# BadAssbasSSynth.net
KiCad netlist of a schematic drawn in EAGLE
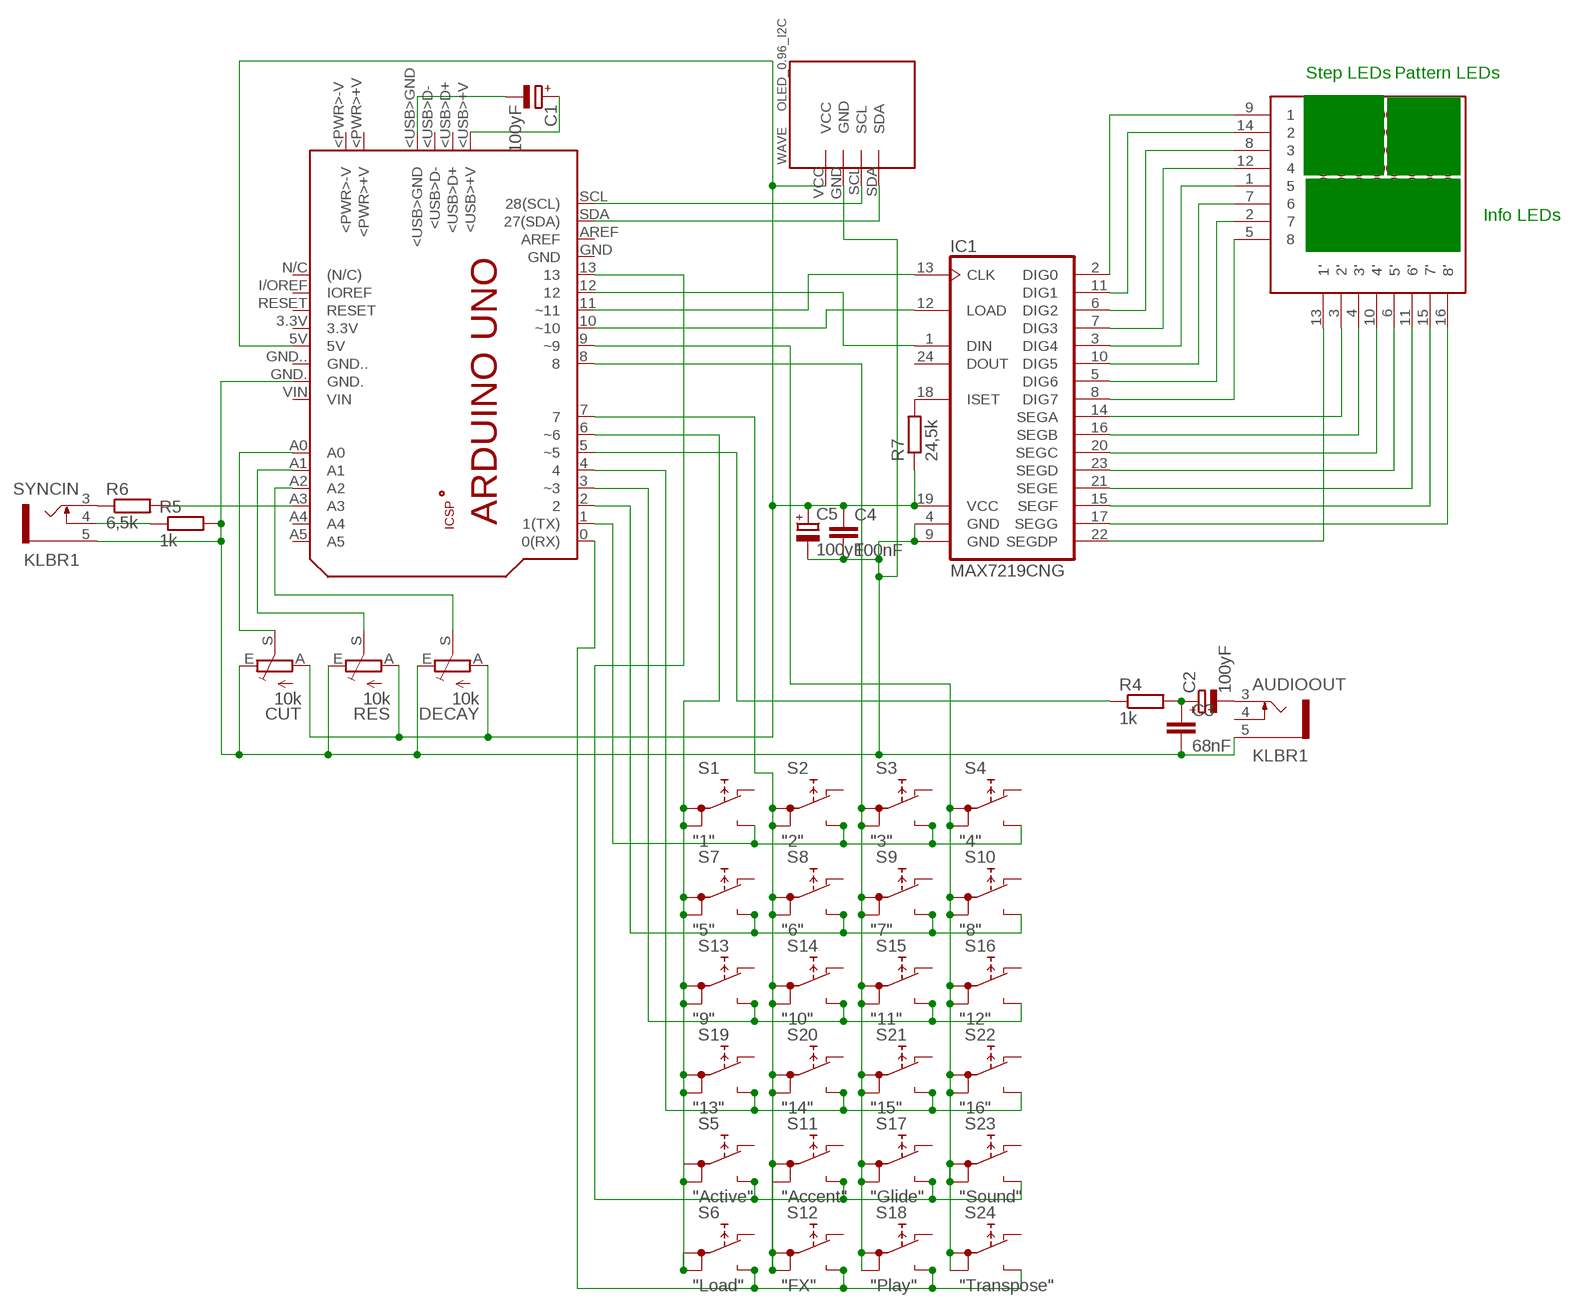
[diagram p0: schematic, sheet 1]

(export (version "E")
  (design (tool "Eeschema 10.0.6"))
  (components
    (comp (ref "AUDIOOUT")
      (value "KLBR1")
      (footprint "eagle-import:KLBR1")
      (fields (field (name "MPN") "KLBR 1"))
      (libsource (lib "eagle-import") (part "KLBR?1"))
    )
    (comp (ref "C1")
      (value "100yF")
      (footprint "eagle-import:E2,5-6E")
      (libsource (lib "eagle-import") (part "CPOL-EUE2,5-6E"))
    )
    (comp (ref "C2")
      (value "100yF")
      (footprint "eagle-import:E2,5-6E")
      (libsource (lib "eagle-import") (part "CPOL-EUE2,5-6E"))
    )
    (comp (ref "C3")
      (value "68nF")
      (footprint "eagle-import:C025-025X050")
      (libsource (lib "eagle-import") (part "C-EU025-025X050"))
    )
    (comp (ref "C4")
      (value "100nF")
      (footprint "eagle-import:C025-025X050")
      (libsource (lib "eagle-import") (part "C-EU025-025X050"))
    )
    (comp (ref "C5")
      (value "100yF")
      (footprint "eagle-import:E2,5-6E")
      (libsource (lib "eagle-import") (part "CPOL-EUE2,5-6E"))
    )
    (comp (ref "CUT")
      (value "10k")
      (footprint "eagle-import:CIP20C-6MM")
      (libsource (lib "eagle-import") (part "TRIM_EU-CIP20C-6MM"))
    )
    (comp (ref "DECAY")
      (value "10k")
      (footprint "eagle-import:CIP20C-6MM")
      (libsource (lib "eagle-import") (part "TRIM_EU-CIP20C-6MM"))
    )
    (comp (ref "IC1")
      (value "MAX7219CNG")
      (footprint "eagle-import:DIL24-3")
      (fields (field (name "MF") "MAXIM"))
      (libsource (lib "eagle-import") (part "MAX7219CNG"))
    )
    (comp (ref "PCB1")
      (value "ARDUINO_UNO")
      (footprint "eagle-import:ARDUINO_UNO")
      (libsource (lib "eagle-import") (part "ARDUINO_UNO"))
    )
    (comp (ref "R4")
      (value "1k")
      (footprint "eagle-import:0204_7")
      (libsource (lib "eagle-import") (part "R-EU_0204/7"))
    )
    (comp (ref "R5")
      (value "1k")
      (footprint "eagle-import:0204_7")
      (libsource (lib "eagle-import") (part "R-EU_0204/7"))
    )
    (comp (ref "R6")
      (value "6,5k")
      (footprint "eagle-import:0204_7")
      (libsource (lib "eagle-import") (part "R-EU_0204/7"))
    )
    (comp (ref "R7")
      (value "24,5k")
      (footprint "eagle-import:0204_7")
      (libsource (lib "eagle-import") (part "R-EU_0204/7"))
    )
    (comp (ref "RES")
      (value "10k")
      (footprint "eagle-import:CIP20C-6MM")
      (libsource (lib "eagle-import") (part "TRIM_EU-CIP20C-6MM"))
    )
    (comp (ref "S1")
      (value "\"1\"")
      (footprint "eagle-import:5501")
      (libsource (lib "eagle-import") (part "55?01"))
    )
    (comp (ref "S2")
      (value "\"2\"")
      (footprint "eagle-import:5501")
      (libsource (lib "eagle-import") (part "55?01"))
    )
    (comp (ref "S3")
      (value "\"3\"")
      (footprint "eagle-import:5501")
      (libsource (lib "eagle-import") (part "55?01"))
    )
    (comp (ref "S4")
      (value "\"4\"")
      (footprint "eagle-import:5501")
      (libsource (lib "eagle-import") (part "55?01"))
    )
    (comp (ref "S5")
      (value "\"Active\"")
      (footprint "eagle-import:5501")
      (libsource (lib "eagle-import") (part "55?01"))
    )
    (comp (ref "S6")
      (value "\"Load\"")
      (footprint "eagle-import:5501")
      (libsource (lib "eagle-import") (part "55?01"))
    )
    (comp (ref "S7")
      (value "\"5\"")
      (footprint "eagle-import:5501")
      (libsource (lib "eagle-import") (part "55?01"))
    )
    (comp (ref "S8")
      (value "\"6\"")
      (footprint "eagle-import:5501")
      (libsource (lib "eagle-import") (part "55?01"))
    )
    (comp (ref "S9")
      (value "\"7\"")
      (footprint "eagle-import:5501")
      (libsource (lib "eagle-import") (part "55?01"))
    )
    (comp (ref "S10")
      (value "\"8\"")
      (footprint "eagle-import:5501")
      (libsource (lib "eagle-import") (part "55?01"))
    )
    (comp (ref "S11")
      (value "\"Accent\"")
      (footprint "eagle-import:5501")
      (libsource (lib "eagle-import") (part "55?01"))
    )
    (comp (ref "S12")
      (value "\"FX\"")
      (footprint "eagle-import:5501")
      (libsource (lib "eagle-import") (part "55?01"))
    )
    (comp (ref "S13")
      (value "\"9\"")
      (footprint "eagle-import:5501")
      (libsource (lib "eagle-import") (part "55?01"))
    )
    (comp (ref "S14")
      (value "\"10\"")
      (footprint "eagle-import:5501")
      (libsource (lib "eagle-import") (part "55?01"))
    )
    (comp (ref "S15")
      (value "\"11\"")
      (footprint "eagle-import:5501")
      (libsource (lib "eagle-import") (part "55?01"))
    )
    (comp (ref "S16")
      (value "\"12\"")
      (footprint "eagle-import:5501")
      (libsource (lib "eagle-import") (part "55?01"))
    )
    (comp (ref "S17")
      (value "\"Glide\"")
      (footprint "eagle-import:5501")
      (libsource (lib "eagle-import") (part "55?01"))
    )
    (comp (ref "S18")
      (value "\"Play\"")
      (footprint "eagle-import:5501")
      (libsource (lib "eagle-import") (part "55?01"))
    )
    (comp (ref "S19")
      (value "\"13\"")
      (footprint "eagle-import:5501")
      (libsource (lib "eagle-import") (part "55?01"))
    )
    (comp (ref "S20")
      (value "\"14\"")
      (footprint "eagle-import:5501")
      (libsource (lib "eagle-import") (part "55?01"))
    )
    (comp (ref "S21")
      (value "\"15\"")
      (footprint "eagle-import:5501")
      (libsource (lib "eagle-import") (part "55?01"))
    )
    (comp (ref "S22")
      (value "\"16\"")
      (footprint "eagle-import:5501")
      (libsource (lib "eagle-import") (part "55?01"))
    )
    (comp (ref "S23")
      (value "\"Sound\"")
      (footprint "eagle-import:5501")
      (libsource (lib "eagle-import") (part "55?01"))
    )
    (comp (ref "S24")
      (value "\"Transpose\"")
      (footprint "eagle-import:5501")
      (libsource (lib "eagle-import") (part "55?01"))
    )
    (comp (ref "SYNCIN")
      (value "KLBR1")
      (footprint "eagle-import:KLBR1")
      (fields (field (name "MPN") "KLBR 1"))
      (libsource (lib "eagle-import") (part "KLBR?1"))
    )
    (comp (ref "U$2")
      (value "NFM-12881BG-11")
      (footprint "eagle-import:NFM-12881BG-11")
      (libsource (lib "eagle-import") (part "NFM-12881BG-11"))
    )
    (comp (ref "WAVE")
      (value "OLED_0.96_I2C")
      (footprint "eagle-import:OLED_0.96_I2C")
      (libsource (lib "eagle-import") (part "OLED_0.96_I2C"))
    )
  )
  (nets
    (net (code "1") (name "Net-(AUDIOOUT-Pad3)") (class "Default")
      (node (ref "AUDIOOUT") (pin "3") (pinfunction "3_3") (pintype "passive"))
      (node (ref "C2") (pin "-") (pinfunction "-_-") (pintype "passive"))
    )
    (net (code "2") (name "Net-(AUDIOOUT-Pad5)") (class "Default")
      (node (ref "AUDIOOUT") (pin "5") (pinfunction "5_5") (pintype "passive"))
      (node (ref "C3") (pin "2") (pinfunction "2_2") (pintype "passive"))
      (node (ref "C4") (pin "2") (pinfunction "2_2") (pintype "passive"))
      (node (ref "C5") (pin "-") (pinfunction "-_-") (pintype "passive"))
      (node (ref "CUT") (pin "E") (pinfunction "E_E") (pintype "passive"))
      (node (ref "DECAY") (pin "E") (pinfunction "E_E") (pintype "passive"))
      (node (ref "IC1") (pin "4") (pinfunction "GND_4") (pintype "power_in"))
      (node (ref "IC1") (pin "9") (pinfunction "GND_9") (pintype "power_in"))
      (node (ref "PCB1") (pin "GND.") (pinfunction "GND._GND.") (pintype "bidirectional"))
      (node (ref "R5") (pin "2") (pinfunction "2_2") (pintype "passive"))
      (node (ref "RES") (pin "E") (pinfunction "E_E") (pintype "passive"))
      (node (ref "SYNCIN") (pin "5") (pinfunction "5_5") (pintype "passive"))
      (node (ref "WAVE") (pin "GND") (pinfunction "GND_GND") (pintype "bidirectional"))
    )
    (net (code "3") (name "Net-(C1-Pad+)") (class "Default")
      (node (ref "C1") (pin "+") (pinfunction "+_+") (pintype "passive"))
      (node (ref "PCB1") (pin "<USB>+V") (pinfunction "<USB>+V_<USB>+V") (pintype "bidirectional"))
    )
    (net (code "4") (name "Net-(C1-Pad-)") (class "Default")
      (node (ref "C1") (pin "-") (pinfunction "-_-") (pintype "passive"))
      (node (ref "PCB1") (pin "<USB>GND") (pinfunction "<USB>GND_<USB>GND") (pintype "bidirectional"))
    )
    (net (code "5") (name "Net-(C2-Pad+)") (class "Default")
      (node (ref "C2") (pin "+") (pinfunction "+_+") (pintype "passive"))
      (node (ref "C3") (pin "1") (pinfunction "1_1") (pintype "passive"))
      (node (ref "R4") (pin "2") (pinfunction "2_2") (pintype "passive"))
    )
    (net (code "6") (name "Net-(CUT-PadS)") (class "Default")
      (node (ref "CUT") (pin "S") (pinfunction "S_S") (pintype "passive"))
      (node (ref "PCB1") (pin "A0") (pinfunction "A0_A0") (pintype "bidirectional"))
    )
    (net (code "7") (name "Net-(DECAY-PadS)") (class "Default")
      (node (ref "DECAY") (pin "S") (pinfunction "S_S") (pintype "passive"))
      (node (ref "PCB1") (pin "A2") (pinfunction "A2_A2") (pintype "bidirectional"))
    )
    (net (code "8") (name "Net-(IC1-CLK)") (class "Default")
      (node (ref "IC1") (pin "13") (pinfunction "CLK_13") (pintype "input"))
      (node (ref "PCB1") (pin "11") (pinfunction "~{11}_11") (pintype "bidirectional"))
    )
    (net (code "9") (name "Net-(IC1-DIG0)") (class "Default")
      (node (ref "IC1") (pin "2") (pinfunction "DIG0_2") (pintype "output"))
      (node (ref "U$2") (pin "9") (pinfunction "1_9") (pintype "input"))
    )
    (net (code "10") (name "Net-(IC1-DIG1)") (class "Default")
      (node (ref "IC1") (pin "11") (pinfunction "DIG1_11") (pintype "output"))
      (node (ref "U$2") (pin "14") (pinfunction "2_14") (pintype "input"))
    )
    (net (code "11") (name "Net-(IC1-DIG2)") (class "Default")
      (node (ref "IC1") (pin "6") (pinfunction "DIG2_6") (pintype "output"))
      (node (ref "U$2") (pin "8") (pinfunction "3_8") (pintype "input"))
    )
    (net (code "12") (name "Net-(IC1-DIG3)") (class "Default")
      (node (ref "IC1") (pin "7") (pinfunction "DIG3_7") (pintype "output"))
      (node (ref "U$2") (pin "12") (pinfunction "4_12") (pintype "input"))
    )
    (net (code "13") (name "Net-(IC1-DIG4)") (class "Default")
      (node (ref "IC1") (pin "3") (pinfunction "DIG4_3") (pintype "output"))
      (node (ref "U$2") (pin "1") (pinfunction "5_1") (pintype "input"))
    )
    (net (code "14") (name "Net-(IC1-DIG5)") (class "Default")
      (node (ref "IC1") (pin "10") (pinfunction "DIG5_10") (pintype "output"))
      (node (ref "U$2") (pin "7") (pinfunction "6_7") (pintype "input"))
    )
    (net (code "15") (name "Net-(IC1-DIG6)") (class "Default")
      (node (ref "IC1") (pin "5") (pinfunction "DIG6_5") (pintype "output"))
      (node (ref "U$2") (pin "2") (pinfunction "7_2") (pintype "input"))
    )
    (net (code "16") (name "Net-(IC1-DIG7)") (class "Default")
      (node (ref "IC1") (pin "8") (pinfunction "DIG7_8") (pintype "output"))
      (node (ref "U$2") (pin "5") (pinfunction "8_5") (pintype "input"))
    )
    (net (code "17") (name "Net-(IC1-DIN)") (class "Default")
      (node (ref "IC1") (pin "1") (pinfunction "DIN_1") (pintype "input"))
      (node (ref "PCB1") (pin "12") (pinfunction "12_12") (pintype "bidirectional"))
    )
    (net (code "18") (name "Net-(IC1-ISET)") (class "Default")
      (node (ref "IC1") (pin "18") (pinfunction "ISET_18") (pintype "input"))
      (node (ref "R7") (pin "2") (pinfunction "2_2") (pintype "passive"))
    )
    (net (code "19") (name "Net-(IC1-LOAD)") (class "Default")
      (node (ref "IC1") (pin "12") (pinfunction "LOAD_12") (pintype "input"))
      (node (ref "PCB1") (pin "10") (pinfunction "~{10}_10") (pintype "bidirectional"))
    )
    (net (code "20") (name "Net-(IC1-SEGA)") (class "Default")
      (node (ref "IC1") (pin "14") (pinfunction "SEGA_14") (pintype "output"))
      (node (ref "U$2") (pin "3") (pinfunction "2'_3") (pintype "output"))
    )
    (net (code "21") (name "Net-(IC1-SEGB)") (class "Default")
      (node (ref "IC1") (pin "16") (pinfunction "SEGB_16") (pintype "output"))
      (node (ref "U$2") (pin "4") (pinfunction "3'_4") (pintype "output"))
    )
    (net (code "22") (name "Net-(IC1-SEGC)") (class "Default")
      (node (ref "IC1") (pin "20") (pinfunction "SEGC_20") (pintype "output"))
      (node (ref "U$2") (pin "10") (pinfunction "4'_10") (pintype "output"))
    )
    (net (code "23") (name "Net-(IC1-SEGD)") (class "Default")
      (node (ref "IC1") (pin "23") (pinfunction "SEGD_23") (pintype "output"))
      (node (ref "U$2") (pin "6") (pinfunction "5'_6") (pintype "output"))
    )
    (net (code "24") (name "Net-(IC1-SEGDP)") (class "Default")
      (node (ref "IC1") (pin "22") (pinfunction "SEGDP_22") (pintype "output"))
      (node (ref "U$2") (pin "13") (pinfunction "1'_13") (pintype "output"))
    )
    (net (code "25") (name "Net-(IC1-SEGE)") (class "Default")
      (node (ref "IC1") (pin "21") (pinfunction "SEGE_21") (pintype "output"))
      (node (ref "U$2") (pin "11") (pinfunction "6'_11") (pintype "output"))
    )
    (net (code "26") (name "Net-(IC1-SEGF)") (class "Default")
      (node (ref "IC1") (pin "15") (pinfunction "SEGF_15") (pintype "output"))
      (node (ref "U$2") (pin "15") (pinfunction "7'_15") (pintype "output"))
    )
    (net (code "27") (name "Net-(IC1-SEGG)") (class "Default")
      (node (ref "IC1") (pin "17") (pinfunction "SEGG_17") (pintype "output"))
      (node (ref "U$2") (pin "16") (pinfunction "8'_16") (pintype "output"))
    )
    (net (code "28") (name "Net-(IC1-VCC)") (class "Default")
      (node (ref "C4") (pin "1") (pinfunction "1_1") (pintype "passive"))
      (node (ref "C5") (pin "+") (pinfunction "+_+") (pintype "passive"))
      (node (ref "CUT") (pin "A") (pinfunction "A_A") (pintype "passive"))
      (node (ref "DECAY") (pin "A") (pinfunction "A_A") (pintype "passive"))
      (node (ref "IC1") (pin "19") (pinfunction "VCC_19") (pintype "power_in"))
      (node (ref "PCB1") (pin "5V") (pinfunction "5V_5V") (pintype "bidirectional"))
      (node (ref "R7") (pin "1") (pinfunction "1_1") (pintype "passive"))
      (node (ref "RES") (pin "A") (pinfunction "A_A") (pintype "passive"))
      (node (ref "WAVE") (pin "VCC") (pinfunction "VCC_VCC") (pintype "bidirectional"))
    )
    (net (code "29") (name "Net-(PCB1-0(RX))") (class "Default")
      (node (ref "PCB1") (pin "0") (pinfunction "0(RX)_0") (pintype "bidirectional"))
      (node (ref "S12") (pin "NO") (pinfunction "NO_NO") (pintype "passive"))
      (node (ref "S18") (pin "NO") (pinfunction "NO_NO") (pintype "passive"))
      (node (ref "S24") (pin "NO") (pinfunction "NO_NO") (pintype "passive"))
      (node (ref "S6") (pin "NO") (pinfunction "NO_NO") (pintype "passive"))
    )
    (net (code "30") (name "Net-(PCB1-1(TX))") (class "Default")
      (node (ref "PCB1") (pin "1") (pinfunction "1(TX)_1") (pintype "bidirectional"))
      (node (ref "S1") (pin "NO") (pinfunction "NO_NO") (pintype "passive"))
      (node (ref "S2") (pin "NO") (pinfunction "NO_NO") (pintype "passive"))
      (node (ref "S3") (pin "NO") (pinfunction "NO_NO") (pintype "passive"))
      (node (ref "S4") (pin "NO") (pinfunction "NO_NO") (pintype "passive"))
    )
    (net (code "31") (name "Net-(PCB1-27(SDA))") (class "Default")
      (node (ref "PCB1") (pin "SDA") (pinfunction "27(SDA)_SDA") (pintype "bidirectional"))
      (node (ref "WAVE") (pin "SDA") (pinfunction "SDA_SDA") (pintype "bidirectional"))
    )
    (net (code "32") (name "Net-(PCB1-28(SCL))") (class "Default")
      (node (ref "PCB1") (pin "SCL") (pinfunction "28(SCL)_SCL") (pintype "bidirectional"))
      (node (ref "WAVE") (pin "SCL") (pinfunction "SCL_SCL") (pintype "bidirectional"))
    )
    (net (code "33") (name "Net-(PCB1-Pad2)") (class "Default")
      (node (ref "PCB1") (pin "2") (pinfunction "2_2") (pintype "bidirectional"))
      (node (ref "S10") (pin "NO") (pinfunction "NO_NO") (pintype "passive"))
      (node (ref "S7") (pin "NO") (pinfunction "NO_NO") (pintype "passive"))
      (node (ref "S8") (pin "NO") (pinfunction "NO_NO") (pintype "passive"))
      (node (ref "S9") (pin "NO") (pinfunction "NO_NO") (pintype "passive"))
    )
    (net (code "34") (name "Net-(PCB1-Pad4)") (class "Default")
      (node (ref "PCB1") (pin "4") (pinfunction "4_4") (pintype "bidirectional"))
      (node (ref "S19") (pin "NO") (pinfunction "NO_NO") (pintype "passive"))
      (node (ref "S20") (pin "NO") (pinfunction "NO_NO") (pintype "passive"))
      (node (ref "S21") (pin "NO") (pinfunction "NO_NO") (pintype "passive"))
      (node (ref "S22") (pin "NO") (pinfunction "NO_NO") (pintype "passive"))
    )
    (net (code "35") (name "Net-(PCB1-Pad7)") (class "Default")
      (node (ref "PCB1") (pin "7") (pinfunction "7_7") (pintype "bidirectional"))
      (node (ref "S11") (pin "1A") (pinfunction "1A_1A") (pintype "passive"))
      (node (ref "S11") (pin "1B") (pinfunction "1B_1B") (pintype "passive"))
      (node (ref "S12") (pin "1A") (pinfunction "1A_1A") (pintype "passive"))
      (node (ref "S12") (pin "1B") (pinfunction "1B_1B") (pintype "passive"))
      (node (ref "S14") (pin "1A") (pinfunction "1A_1A") (pintype "passive"))
      (node (ref "S14") (pin "1B") (pinfunction "1B_1B") (pintype "passive"))
      (node (ref "S2") (pin "1A") (pinfunction "1A_1A") (pintype "passive"))
      (node (ref "S2") (pin "1B") (pinfunction "1B_1B") (pintype "passive"))
      (node (ref "S20") (pin "1A") (pinfunction "1A_1A") (pintype "passive"))
      (node (ref "S20") (pin "1B") (pinfunction "1B_1B") (pintype "passive"))
      (node (ref "S8") (pin "1A") (pinfunction "1A_1A") (pintype "passive"))
      (node (ref "S8") (pin "1B") (pinfunction "1B_1B") (pintype "passive"))
    )
    (net (code "36") (name "Net-(PCB1-Pad8)") (class "Default")
      (node (ref "PCB1") (pin "8") (pinfunction "8_8") (pintype "bidirectional"))
      (node (ref "S15") (pin "1A") (pinfunction "1A_1A") (pintype "passive"))
      (node (ref "S15") (pin "1B") (pinfunction "1B_1B") (pintype "passive"))
      (node (ref "S17") (pin "1A") (pinfunction "1A_1A") (pintype "passive"))
      (node (ref "S17") (pin "1B") (pinfunction "1B_1B") (pintype "passive"))
      (node (ref "S18") (pin "1A") (pinfunction "1A_1A") (pintype "passive"))
      (node (ref "S18") (pin "1B") (pinfunction "1B_1B") (pintype "passive"))
      (node (ref "S21") (pin "1A") (pinfunction "1A_1A") (pintype "passive"))
      (node (ref "S21") (pin "1B") (pinfunction "1B_1B") (pintype "passive"))
      (node (ref "S3") (pin "1A") (pinfunction "1A_1A") (pintype "passive"))
      (node (ref "S3") (pin "1B") (pinfunction "1B_1B") (pintype "passive"))
      (node (ref "S9") (pin "1A") (pinfunction "1A_1A") (pintype "passive"))
      (node (ref "S9") (pin "1B") (pinfunction "1B_1B") (pintype "passive"))
    )
    (net (code "37") (name "Net-(PCB1-Pad13)") (class "Default")
      (node (ref "PCB1") (pin "13") (pinfunction "13_13") (pintype "bidirectional"))
      (node (ref "S11") (pin "NO") (pinfunction "NO_NO") (pintype "passive"))
      (node (ref "S17") (pin "NO") (pinfunction "NO_NO") (pintype "passive"))
      (node (ref "S23") (pin "NO") (pinfunction "NO_NO") (pintype "passive"))
      (node (ref "S5") (pin "NO") (pinfunction "NO_NO") (pintype "passive"))
    )
    (net (code "38") (name "Net-(PCB1-PadA1)") (class "Default")
      (node (ref "PCB1") (pin "A1") (pinfunction "A1_A1") (pintype "bidirectional"))
      (node (ref "RES") (pin "S") (pinfunction "S_S") (pintype "passive"))
    )
    (net (code "39") (name "Net-(PCB1-PadA3)") (class "Default")
      (node (ref "PCB1") (pin "A3") (pinfunction "A3_A3") (pintype "bidirectional"))
      (node (ref "R6") (pin "2") (pinfunction "2_2") (pintype "passive"))
    )
    (net (code "40") (name "Net-(PCB1-~{3})") (class "Default")
      (node (ref "PCB1") (pin "3") (pinfunction "~{3}_3") (pintype "bidirectional"))
      (node (ref "S13") (pin "NO") (pinfunction "NO_NO") (pintype "passive"))
      (node (ref "S14") (pin "NO") (pinfunction "NO_NO") (pintype "passive"))
      (node (ref "S15") (pin "NO") (pinfunction "NO_NO") (pintype "passive"))
      (node (ref "S16") (pin "NO") (pinfunction "NO_NO") (pintype "passive"))
    )
    (net (code "41") (name "Net-(PCB1-~{5})") (class "Default")
      (node (ref "PCB1") (pin "5") (pinfunction "~{5}_5") (pintype "bidirectional"))
      (node (ref "R4") (pin "1") (pinfunction "1_1") (pintype "passive"))
    )
    (net (code "42") (name "Net-(PCB1-~{6})") (class "Default")
      (node (ref "PCB1") (pin "6") (pinfunction "~{6}_6") (pintype "bidirectional"))
      (node (ref "S1") (pin "1A") (pinfunction "1A_1A") (pintype "passive"))
      (node (ref "S1") (pin "1B") (pinfunction "1B_1B") (pintype "passive"))
      (node (ref "S13") (pin "1A") (pinfunction "1A_1A") (pintype "passive"))
      (node (ref "S13") (pin "1B") (pinfunction "1B_1B") (pintype "passive"))
      (node (ref "S19") (pin "1A") (pinfunction "1A_1A") (pintype "passive"))
      (node (ref "S19") (pin "1B") (pinfunction "1B_1B") (pintype "passive"))
      (node (ref "S5") (pin "1A") (pinfunction "1A_1A") (pintype "passive"))
      (node (ref "S5") (pin "1B") (pinfunction "1B_1B") (pintype "passive"))
      (node (ref "S6") (pin "1A") (pinfunction "1A_1A") (pintype "passive"))
      (node (ref "S6") (pin "1B") (pinfunction "1B_1B") (pintype "passive"))
      (node (ref "S7") (pin "1A") (pinfunction "1A_1A") (pintype "passive"))
      (node (ref "S7") (pin "1B") (pinfunction "1B_1B") (pintype "passive"))
    )
    (net (code "43") (name "Net-(PCB1-~{9})") (class "Default")
      (node (ref "PCB1") (pin "9") (pinfunction "~{9}_9") (pintype "bidirectional"))
      (node (ref "S10") (pin "1A") (pinfunction "1A_1A") (pintype "passive"))
      (node (ref "S10") (pin "1B") (pinfunction "1B_1B") (pintype "passive"))
      (node (ref "S16") (pin "1A") (pinfunction "1A_1A") (pintype "passive"))
      (node (ref "S16") (pin "1B") (pinfunction "1B_1B") (pintype "passive"))
      (node (ref "S22") (pin "1A") (pinfunction "1A_1A") (pintype "passive"))
      (node (ref "S22") (pin "1B") (pinfunction "1B_1B") (pintype "passive"))
      (node (ref "S23") (pin "1A") (pinfunction "1A_1A") (pintype "passive"))
      (node (ref "S23") (pin "1B") (pinfunction "1B_1B") (pintype "passive"))
      (node (ref "S24") (pin "1A") (pinfunction "1A_1A") (pintype "passive"))
      (node (ref "S24") (pin "1B") (pinfunction "1B_1B") (pintype "passive"))
      (node (ref "S4") (pin "1A") (pinfunction "1A_1A") (pintype "passive"))
      (node (ref "S4") (pin "1B") (pinfunction "1B_1B") (pintype "passive"))
    )
    (net (code "44") (name "Net-(R5-Pad1)") (class "Default")
      (node (ref "R5") (pin "1") (pinfunction "1_1") (pintype "passive"))
      (node (ref "SYNCIN") (pin "4") (pinfunction "4_4") (pintype "passive"))
    )
    (net (code "45") (name "Net-(R6-Pad1)") (class "Default")
      (node (ref "R6") (pin "1") (pinfunction "1_1") (pintype "passive"))
      (node (ref "SYNCIN") (pin "3") (pinfunction "3_3") (pintype "passive"))
    )
    (net (code "46") (name "unconnected-(AUDIOOUT-Pad4)") (class "Default")
      (node (ref "AUDIOOUT") (pin "4") (pinfunction "4_4") (pintype "passive"))
    )
    (net (code "47") (name "unconnected-(IC1-DOUT-Pad24)") (class "Default")
      (node (ref "IC1") (pin "24") (pinfunction "DOUT_24") (pintype "output"))
    )
    (net (code "48") (name "unconnected-(PCB1-(N{slash}C)-PadN{slash}C)") (class "Default")
      (node (ref "PCB1") (pin "N/C") (pinfunction "(N/C)_N/C") (pintype "bidirectional"))
    )
    (net (code "49") (name "unconnected-(PCB1-IOREF-PadI{slash}OREF)") (class "Default")
      (node (ref "PCB1") (pin "I/OREF") (pinfunction "IOREF_I/OREF") (pintype "bidirectional"))
    )
    (net (code "50") (name "unconnected-(PCB1-Pad+5V)") (class "Default")
      (node (ref "PCB1") (pin "+5V") (pinfunction "+5V_+5V") (pintype "bidirectional"))
    )
    (net (code "51") (name "unconnected-(PCB1-Pad3.3V)") (class "Default")
      (node (ref "PCB1") (pin "3.3V") (pinfunction "3.3V_3.3V") (pintype "bidirectional"))
    )
    (net (code "52") (name "unconnected-(PCB1-Pad<PWR>+V)") (class "Default")
      (node (ref "PCB1") (pin "<PWR>+V") (pinfunction "<PWR>+V_<PWR>+V") (pintype "bidirectional"))
    )
    (net (code "53") (name "unconnected-(PCB1-Pad<PWR>-V)") (class "Default")
      (node (ref "PCB1") (pin "<PWR>-V") (pinfunction "<PWR>-V_<PWR>-V") (pintype "bidirectional"))
    )
    (net (code "54") (name "unconnected-(PCB1-Pad<USB>D+)") (class "Default")
      (node (ref "PCB1") (pin "<USB>D+") (pinfunction "<USB>D+_<USB>D+") (pintype "bidirectional"))
    )
    (net (code "55") (name "unconnected-(PCB1-Pad<USB>D-)") (class "Default")
      (node (ref "PCB1") (pin "<USB>D-") (pinfunction "<USB>D-_<USB>D-") (pintype "bidirectional"))
    )
    (net (code "56") (name "unconnected-(PCB1-PadA4)") (class "Default")
      (node (ref "PCB1") (pin "A4") (pinfunction "A4_A4") (pintype "bidirectional"))
    )
    (net (code "57") (name "unconnected-(PCB1-PadA5)") (class "Default")
      (node (ref "PCB1") (pin "A5") (pinfunction "A5_A5") (pintype "bidirectional"))
    )
    (net (code "58") (name "unconnected-(PCB1-PadAREF)") (class "Default")
      (node (ref "PCB1") (pin "AREF") (pinfunction "AREF_AREF") (pintype "bidirectional"))
    )
    (net (code "59") (name "unconnected-(PCB1-PadGND)") (class "Default")
      (node (ref "PCB1") (pin "GND") (pinfunction "GND_GND") (pintype "bidirectional"))
    )
    (net (code "60") (name "unconnected-(PCB1-PadGND..)") (class "Default")
      (node (ref "PCB1") (pin "GND..") (pinfunction "GND.._GND..") (pintype "bidirectional"))
    )
    (net (code "61") (name "unconnected-(PCB1-PadGND_)") (class "Default")
      (node (ref "PCB1") (pin "GND_") (pinfunction "GND__GND_") (pintype "bidirectional"))
    )
    (net (code "62") (name "unconnected-(PCB1-PadMISO)") (class "Default")
      (node (ref "PCB1") (pin "MISO") (pinfunction "MISO_MISO") (pintype "bidirectional"))
    )
    (net (code "63") (name "unconnected-(PCB1-PadMOSI)") (class "Default")
      (node (ref "PCB1") (pin "MOSI") (pinfunction "MOSI_MOSI") (pintype "bidirectional"))
    )
    (net (code "64") (name "unconnected-(PCB1-PadRESET)") (class "Default")
      (node (ref "PCB1") (pin "RESET") (pinfunction "RESET_RESET") (pintype "bidirectional"))
    )
    (net (code "65") (name "unconnected-(PCB1-PadRESET.)") (class "Default")
      (node (ref "PCB1") (pin "RESET.") (pinfunction "RESET._RESET.") (pintype "bidirectional"))
    )
    (net (code "66") (name "unconnected-(PCB1-PadSCK)") (class "Default")
      (node (ref "PCB1") (pin "SCK") (pinfunction "SCK_SCK") (pintype "bidirectional"))
    )
    (net (code "67") (name "unconnected-(PCB1-PadVIN)") (class "Default")
      (node (ref "PCB1") (pin "VIN") (pinfunction "VIN_VIN") (pintype "bidirectional"))
    )
    (net (code "68") (name "unconnected-(S1-PadNC)") (class "Default")
      (node (ref "S1") (pin "NC") (pinfunction "NC_NC") (pintype "passive"))
    )
    (net (code "69") (name "unconnected-(S2-PadNC)") (class "Default")
      (node (ref "S2") (pin "NC") (pinfunction "NC_NC") (pintype "passive"))
    )
    (net (code "70") (name "unconnected-(S3-PadNC)") (class "Default")
      (node (ref "S3") (pin "NC") (pinfunction "NC_NC") (pintype "passive"))
    )
    (net (code "71") (name "unconnected-(S4-PadNC)") (class "Default")
      (node (ref "S4") (pin "NC") (pinfunction "NC_NC") (pintype "passive"))
    )
    (net (code "72") (name "unconnected-(S5-PadNC)") (class "Default")
      (node (ref "S5") (pin "NC") (pinfunction "NC_NC") (pintype "passive"))
    )
    (net (code "73") (name "unconnected-(S6-PadNC)") (class "Default")
      (node (ref "S6") (pin "NC") (pinfunction "NC_NC") (pintype "passive"))
    )
    (net (code "74") (name "unconnected-(S7-PadNC)") (class "Default")
      (node (ref "S7") (pin "NC") (pinfunction "NC_NC") (pintype "passive"))
    )
    (net (code "75") (name "unconnected-(S8-PadNC)") (class "Default")
      (node (ref "S8") (pin "NC") (pinfunction "NC_NC") (pintype "passive"))
    )
    (net (code "76") (name "unconnected-(S9-PadNC)") (class "Default")
      (node (ref "S9") (pin "NC") (pinfunction "NC_NC") (pintype "passive"))
    )
    (net (code "77") (name "unconnected-(S10-PadNC)") (class "Default")
      (node (ref "S10") (pin "NC") (pinfunction "NC_NC") (pintype "passive"))
    )
    (net (code "78") (name "unconnected-(S11-PadNC)") (class "Default")
      (node (ref "S11") (pin "NC") (pinfunction "NC_NC") (pintype "passive"))
    )
    (net (code "79") (name "unconnected-(S12-PadNC)") (class "Default")
      (node (ref "S12") (pin "NC") (pinfunction "NC_NC") (pintype "passive"))
    )
    (net (code "80") (name "unconnected-(S13-PadNC)") (class "Default")
      (node (ref "S13") (pin "NC") (pinfunction "NC_NC") (pintype "passive"))
    )
    (net (code "81") (name "unconnected-(S14-PadNC)") (class "Default")
      (node (ref "S14") (pin "NC") (pinfunction "NC_NC") (pintype "passive"))
    )
    (net (code "82") (name "unconnected-(S15-PadNC)") (class "Default")
      (node (ref "S15") (pin "NC") (pinfunction "NC_NC") (pintype "passive"))
    )
    (net (code "83") (name "unconnected-(S16-PadNC)") (class "Default")
      (node (ref "S16") (pin "NC") (pinfunction "NC_NC") (pintype "passive"))
    )
    (net (code "84") (name "unconnected-(S17-PadNC)") (class "Default")
      (node (ref "S17") (pin "NC") (pinfunction "NC_NC") (pintype "passive"))
    )
    (net (code "85") (name "unconnected-(S18-PadNC)") (class "Default")
      (node (ref "S18") (pin "NC") (pinfunction "NC_NC") (pintype "passive"))
    )
    (net (code "86") (name "unconnected-(S19-PadNC)") (class "Default")
      (node (ref "S19") (pin "NC") (pinfunction "NC_NC") (pintype "passive"))
    )
    (net (code "87") (name "unconnected-(S20-PadNC)") (class "Default")
      (node (ref "S20") (pin "NC") (pinfunction "NC_NC") (pintype "passive"))
    )
    (net (code "88") (name "unconnected-(S21-PadNC)") (class "Default")
      (node (ref "S21") (pin "NC") (pinfunction "NC_NC") (pintype "passive"))
    )
    (net (code "89") (name "unconnected-(S22-PadNC)") (class "Default")
      (node (ref "S22") (pin "NC") (pinfunction "NC_NC") (pintype "passive"))
    )
    (net (code "90") (name "unconnected-(S23-PadNC)") (class "Default")
      (node (ref "S23") (pin "NC") (pinfunction "NC_NC") (pintype "passive"))
    )
    (net (code "91") (name "unconnected-(S24-PadNC)") (class "Default")
      (node (ref "S24") (pin "NC") (pinfunction "NC_NC") (pintype "passive"))
    )
  )
)
